# Esquematico.net
KiCad netlist of a schematic drawn in Altium Designer
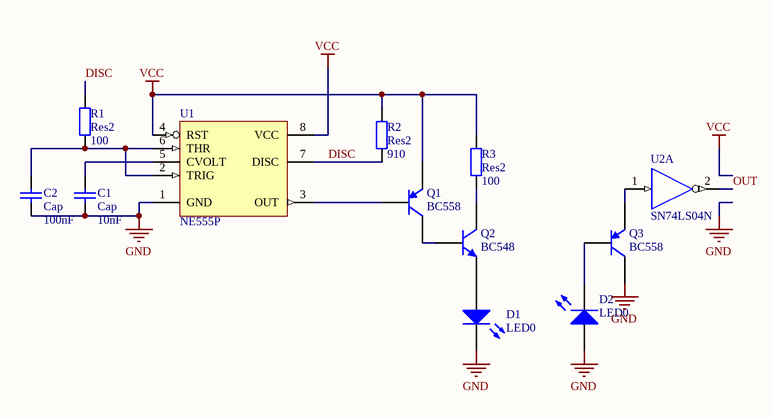
[diagram p0: Esquematico.SchDoc]

(export (version "E")
  (design (tool "Eeschema 10.0.6"))
  (components
    (comp (ref "C1")
      (value "Cap")
      (footprint "RAD-0.2")
      (description "Capacitor")
      (fields (field (name "ALTIUM_VALUE") "10nF") (field (name "PUBLISHER") "Altium Limited"))
      (libsource (lib "Miscellaneous Devices") (part "Cap"))
    )
    (comp (ref "C2")
      (value "Cap")
      (footprint "RAD-0.2")
      (description "Capacitor")
      (fields (field (name "ALTIUM_VALUE") "100nF") (field (name "PUBLISHER") "Altium Limited"))
      (libsource (lib "Miscellaneous Devices") (part "Cap"))
    )
    (comp (ref "D1")
      (value "LED0")
      (footprint "Componentes:LED")
      (description "Typical INFRARED GaAs LED")
      (fields (field (name "PUBLISHER") "Altium Limited"))
      (libsource (lib "Miscellaneous Devices") (part "LED0"))
    )
    (comp (ref "D2")
      (value "LED0")
      (footprint "Componentes:LED")
      (description "Typical INFRARED GaAs LED")
      (fields (field (name "PUBLISHER") "Altium Limited"))
      (libsource (lib "Miscellaneous Devices") (part "LED0"))
    )
    (comp (ref "Q1")
      (value "BC558")
      (footprint "TO-92")
      (description "PNP Bipolar Transistor")
      (fields (field (name "PUBLISHER") "Altium Limited"))
      (libsource (lib "Components") (part "BC558"))
    )
    (comp (ref "Q2")
      (value "BC548")
      (footprint "TO-92")
      (description "NPN General Purpose Amplifier")
      (fields (field (name "PUBLISHER") "Altium Limited"))
      (libsource (lib "Components") (part "BC548"))
    )
    (comp (ref "Q3")
      (value "BC558")
      (footprint "TO-92")
      (description "PNP Bipolar Transistor")
      (fields (field (name "PUBLISHER") "Altium Limited"))
      (libsource (lib "Components") (part "BC558"))
    )
    (comp (ref "R1")
      (value "Res2")
      (footprint "AXIAL-0.4")
      (description "Resistor")
      (fields (field (name "ALTIUM_VALUE") "100") (field (name "PUBLISHER") "Altium Limited"))
      (libsource (lib "Miscellaneous Devices") (part "Res2"))
    )
    (comp (ref "R2")
      (value "Res2")
      (footprint "AXIAL-0.4")
      (description "Resistor")
      (fields (field (name "ALTIUM_VALUE") "910") (field (name "PUBLISHER") "Altium Limited"))
      (libsource (lib "Miscellaneous Devices") (part "Res2"))
    )
    (comp (ref "R3")
      (value "Res2")
      (footprint "AXIAL-0.4")
      (description "Resistor")
      (fields (field (name "ALTIUM_VALUE") "100") (field (name "PUBLISHER") "Altium Limited"))
      (libsource (lib "Miscellaneous Devices") (part "Res2"))
    )
    (comp (ref "U1")
      (value "NE555P")
      (footprint "P008")
      (description "Precision Timer")
      (fields (field (name "PUBLISHER") "Altium Limited"))
      (libsource (lib "TI Analog Timer Circuit") (part "NE555P"))
    )
    (comp (ref "U2")
      (value "SN74LS04N")
      (footprint "N014")
      (description "Hex Inverter")
      (fields (field (name "PUBLISHER") "Altium Limited"))
      (libsource (lib "TI Logic Gate 2") (part "SN74LS04N"))
    )
  )
  (nets
    (net (code "1") (name "/DISC") (class "Default")
      (node (ref "R1") (pin "2") (pinfunction "2_2") (pintype "passive"))
      (node (ref "R2") (pin "1") (pinfunction "1_1") (pintype "passive"))
      (node (ref "U1") (pin "7") (pinfunction "DISC_7") (pintype "open_collector"))
    )
    (net (code "2") (name "/OUT") (class "Default")
      (node (ref "U2") (pin "2") (pinfunction "Y_2") (pintype "output"))
    )
    (net (code "3") (name "GND") (class "Default")
      (node (ref "C1") (pin "1") (pinfunction "1_1") (pintype "passive"))
      (node (ref "C2") (pin "1") (pinfunction "1_1") (pintype "passive"))
      (node (ref "D1") (pin "2") (pinfunction "K_2") (pintype "passive"))
      (node (ref "D2") (pin "1") (pinfunction "A_1") (pintype "passive"))
      (node (ref "Q3") (pin "3") (pinfunction "C_3") (pintype "passive"))
      (node (ref "U1") (pin "1") (pinfunction "GND_1") (pintype "power_in"))
      (node (ref "U2") (pin "7") (pinfunction "GND_7") (pintype "power_in"))
    )
    (net (code "4") (name "Net-(D1-A)") (class "Default")
      (node (ref "D1") (pin "1") (pinfunction "A_1") (pintype "passive"))
      (node (ref "Q2") (pin "1") (pinfunction "E_1") (pintype "passive"))
    )
    (net (code "5") (name "Net-(D2-K)") (class "Default")
      (node (ref "D2") (pin "2") (pinfunction "K_2") (pintype "passive"))
      (node (ref "Q3") (pin "2") (pinfunction "B_2") (pintype "passive"))
    )
    (net (code "6") (name "Net-(Q1-B)") (class "Default")
      (node (ref "Q1") (pin "2") (pinfunction "B_2") (pintype "passive"))
      (node (ref "U1") (pin "3") (pinfunction "OUT_3") (pintype "output"))
    )
    (net (code "7") (name "Net-(Q1-C)") (class "Default")
      (node (ref "Q1") (pin "3") (pinfunction "C_3") (pintype "passive"))
      (node (ref "Q2") (pin "2") (pinfunction "B_2") (pintype "passive"))
    )
    (net (code "8") (name "Net-(Q2-C)") (class "Default")
      (node (ref "Q2") (pin "3") (pinfunction "C_3") (pintype "passive"))
      (node (ref "R3") (pin "1") (pinfunction "1_1") (pintype "passive"))
    )
    (net (code "9") (name "Net-(Q3-E)") (class "Default")
      (node (ref "Q3") (pin "1") (pinfunction "E_1") (pintype "passive"))
      (node (ref "U2") (pin "1") (pinfunction "A_1") (pintype "input"))
    )
    (net (code "10") (name "Net-(U1-CVOLT)") (class "Default")
      (node (ref "C1") (pin "2") (pinfunction "2_2") (pintype "passive"))
      (node (ref "U1") (pin "5") (pinfunction "CVOLT_5") (pintype "passive"))
    )
    (net (code "11") (name "Net-(U1-THR)") (class "Default")
      (node (ref "C2") (pin "2") (pinfunction "2_2") (pintype "passive"))
      (node (ref "R1") (pin "1") (pinfunction "1_1") (pintype "passive"))
      (node (ref "U1") (pin "2") (pinfunction "TRIG_2") (pintype "input"))
      (node (ref "U1") (pin "6") (pinfunction "THR_6") (pintype "input"))
    )
    (net (code "12") (name "VCC") (class "Default")
      (node (ref "Q1") (pin "1") (pinfunction "E_1") (pintype "passive"))
      (node (ref "R2") (pin "2") (pinfunction "2_2") (pintype "passive"))
      (node (ref "R3") (pin "2") (pinfunction "2_2") (pintype "passive"))
      (node (ref "U1") (pin "4") (pinfunction "RST_4") (pintype "input"))
      (node (ref "U1") (pin "8") (pinfunction "VCC_8") (pintype "power_in"))
      (node (ref "U2") (pin "14") (pinfunction "VCC_14") (pintype "power_in"))
    )
  )
)
